# USART.net
KiCad netlist of a schematic drawn in Altium Designer
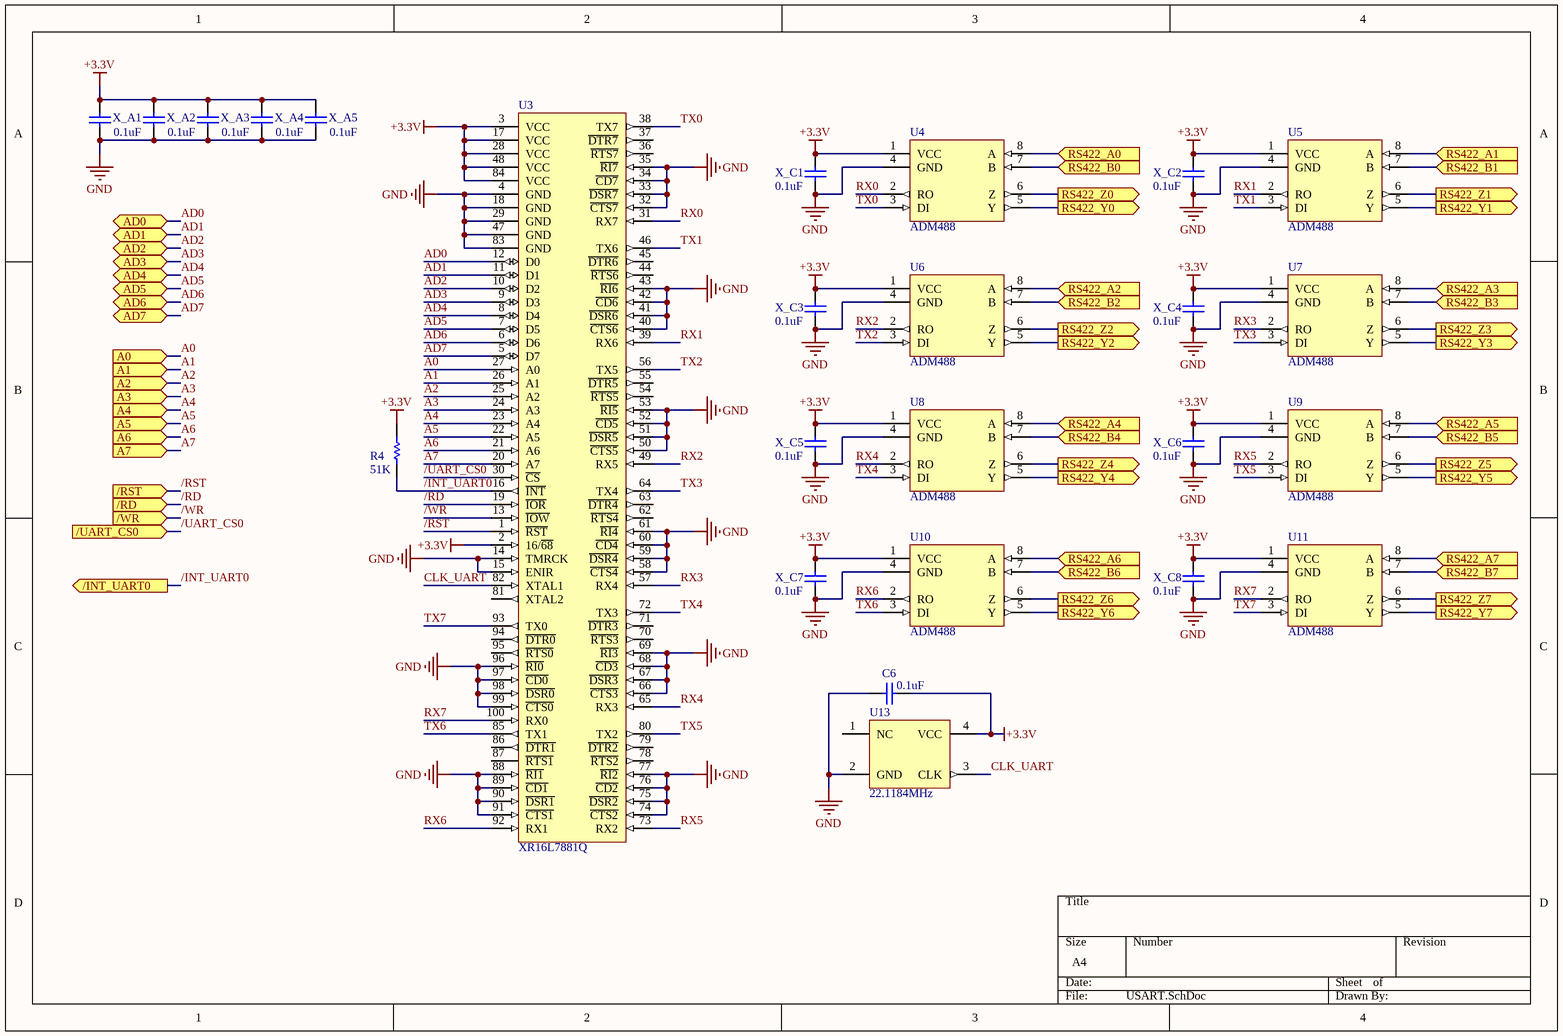
[diagram p0: USART.SchDoc]

(export (version "E")
  (design (tool "Eeschema 10.0.6"))
  (components
    (comp (ref "C6")
      (value "0.1uF")
      (footprint "0805")
      (description "Capacitor")
      (fields (field (name "Comment") "Cap 0.1uf") (field (name "PUBLISHER") "Altium Limited"))
      (libsource (lib "Miscellaneous Devices") (part "Cap"))
    )
    (comp (ref "R4")
      (value "51K")
      (footprint "0805")
      (description "Resistor")
      (fields (field (name "Comment") "51k") (field (name "PUBLISHER") "Altium Limited"))
      (libsource (lib "Miscellaneous Devices") (part "Res1"))
    )
    (comp (ref "U3")
      (value "XR16L7881Q")
      (footprint "QFP65P1800X2400X300-100N_30*20")
      (libsource (lib "cs_Schlib1") (part "my_XR16L7881Q"))
    )
    (comp (ref "U4") (value "ADM488") (footprint "SO-8_L") (libsource (lib "cs_Schlib1") (part "my_ADM488")))
    (comp (ref "U5") (value "ADM488") (footprint "SO-8_L") (libsource (lib "cs_Schlib1") (part "my_ADM488")))
    (comp (ref "U6") (value "ADM488") (footprint "SO-8_L") (libsource (lib "cs_Schlib1") (part "my_ADM488")))
    (comp (ref "U7") (value "ADM488") (footprint "SO-8_L") (libsource (lib "cs_Schlib1") (part "my_ADM488")))
    (comp (ref "U8") (value "ADM488") (footprint "SO-8_L") (libsource (lib "cs_Schlib1") (part "my_ADM488")))
    (comp (ref "U9") (value "ADM488") (footprint "SO-8_L") (libsource (lib "cs_Schlib1") (part "my_ADM488")))
    (comp (ref "U10") (value "ADM488") (footprint "SO-8_L") (libsource (lib "cs_Schlib1") (part "my_ADM488")))
    (comp (ref "U11") (value "ADM488") (footprint "SO-8_L") (libsource (lib "cs_Schlib1") (part "my_ADM488")))
    (comp (ref "U13")
      (value "22.1184MHz")
      (footprint "my_SiT8103")
      (libsource (lib "cs_Schlib1") (part "my_SiT8103"))
    )
    (comp (ref "X_A1")
      (value "0.1uF")
      (footprint "0805")
      (description "Capacitor")
      (fields (field (name "Comment") "Cap 0.1uf") (field (name "PUBLISHER") "Altium Limited"))
      (libsource (lib "Miscellaneous Devices") (part "Cap"))
    )
    (comp (ref "X_A2")
      (value "0.1uF")
      (footprint "0805")
      (description "Capacitor")
      (fields (field (name "Comment") "Cap 0.1uf") (field (name "PUBLISHER") "Altium Limited"))
      (libsource (lib "Miscellaneous Devices") (part "Cap"))
    )
    (comp (ref "X_A3")
      (value "0.1uF")
      (footprint "0805")
      (description "Capacitor")
      (fields (field (name "Comment") "Cap 0.1uf") (field (name "PUBLISHER") "Altium Limited"))
      (libsource (lib "Miscellaneous Devices") (part "Cap"))
    )
    (comp (ref "X_A4")
      (value "0.1uF")
      (footprint "0805")
      (description "Capacitor")
      (fields (field (name "Comment") "Cap 0.1uf") (field (name "PUBLISHER") "Altium Limited"))
      (libsource (lib "Miscellaneous Devices") (part "Cap"))
    )
    (comp (ref "X_A5")
      (value "0.1uF")
      (footprint "0805")
      (description "Capacitor")
      (fields (field (name "Comment") "Cap 0.1uf") (field (name "PUBLISHER") "Altium Limited"))
      (libsource (lib "Miscellaneous Devices") (part "Cap"))
    )
    (comp (ref "X_C1")
      (value "0.1uF")
      (footprint "0805")
      (description "Capacitor")
      (fields (field (name "Comment") "Cap 0.1uf") (field (name "PUBLISHER") "Altium Limited"))
      (libsource (lib "Miscellaneous Devices") (part "Cap"))
    )
    (comp (ref "X_C2")
      (value "0.1uF")
      (footprint "0805")
      (description "Capacitor")
      (fields (field (name "Comment") "Cap 0.1uf") (field (name "PUBLISHER") "Altium Limited"))
      (libsource (lib "Miscellaneous Devices") (part "Cap"))
    )
    (comp (ref "X_C3")
      (value "0.1uF")
      (footprint "0805")
      (description "Capacitor")
      (fields (field (name "Comment") "Cap 0.1uf") (field (name "PUBLISHER") "Altium Limited"))
      (libsource (lib "Miscellaneous Devices") (part "Cap"))
    )
    (comp (ref "X_C4")
      (value "0.1uF")
      (footprint "0805")
      (description "Capacitor")
      (fields (field (name "Comment") "Cap 0.1uf") (field (name "PUBLISHER") "Altium Limited"))
      (libsource (lib "Miscellaneous Devices") (part "Cap"))
    )
    (comp (ref "X_C5")
      (value "0.1uF")
      (footprint "0805")
      (description "Capacitor")
      (fields (field (name "Comment") "Cap 0.1uf") (field (name "PUBLISHER") "Altium Limited"))
      (libsource (lib "Miscellaneous Devices") (part "Cap"))
    )
    (comp (ref "X_C6")
      (value "0.1uF")
      (footprint "0805")
      (description "Capacitor")
      (fields (field (name "Comment") "Cap 0.1uf") (field (name "PUBLISHER") "Altium Limited"))
      (libsource (lib "Miscellaneous Devices") (part "Cap"))
    )
    (comp (ref "X_C7")
      (value "0.1uF")
      (footprint "0805")
      (description "Capacitor")
      (fields (field (name "Comment") "Cap 0.1uf") (field (name "PUBLISHER") "Altium Limited"))
      (libsource (lib "Miscellaneous Devices") (part "Cap"))
    )
    (comp (ref "X_C8")
      (value "0.1uF")
      (footprint "0805")
      (description "Capacitor")
      (fields (field (name "Comment") "Cap 0.1uf") (field (name "PUBLISHER") "Altium Limited"))
      (libsource (lib "Miscellaneous Devices") (part "Cap"))
    )
  )
  (nets
    (net (code "1") (name "+3.3V") (class "Default")
      (node (ref "C6") (pin "1") (pinfunction "1_1") (pintype "passive"))
      (node (ref "R4") (pin "2") (pinfunction "2_2") (pintype "passive"))
      (node (ref "U10") (pin "1") (pinfunction "VCC_1") (pintype "power_in"))
      (node (ref "U11") (pin "1") (pinfunction "VCC_1") (pintype "power_in"))
      (node (ref "U13") (pin "4") (pinfunction "VCC_4") (pintype "power_in"))
      (node (ref "U3") (pin "17") (pinfunction "VCC_17") (pintype "power_in"))
      (node (ref "U3") (pin "2") (pinfunction "16/~{68}_2") (pintype "input"))
      (node (ref "U3") (pin "28") (pinfunction "VCC_28") (pintype "power_in"))
      (node (ref "U3") (pin "3") (pinfunction "VCC_3") (pintype "power_in"))
      (node (ref "U3") (pin "48") (pinfunction "VCC_48") (pintype "power_in"))
      (node (ref "U3") (pin "84") (pinfunction "VCC_84") (pintype "power_in"))
      (node (ref "U4") (pin "1") (pinfunction "VCC_1") (pintype "power_in"))
      (node (ref "U5") (pin "1") (pinfunction "VCC_1") (pintype "power_in"))
      (node (ref "U6") (pin "1") (pinfunction "VCC_1") (pintype "power_in"))
      (node (ref "U7") (pin "1") (pinfunction "VCC_1") (pintype "power_in"))
      (node (ref "U8") (pin "1") (pinfunction "VCC_1") (pintype "power_in"))
      (node (ref "U9") (pin "1") (pinfunction "VCC_1") (pintype "power_in"))
      (node (ref "X_A1") (pin "2") (pinfunction "2_2") (pintype "passive"))
      (node (ref "X_A2") (pin "2") (pinfunction "2_2") (pintype "passive"))
      (node (ref "X_A3") (pin "2") (pinfunction "2_2") (pintype "passive"))
      (node (ref "X_A4") (pin "2") (pinfunction "2_2") (pintype "passive"))
      (node (ref "X_A5") (pin "2") (pinfunction "2_2") (pintype "passive"))
      (node (ref "X_C1") (pin "2") (pinfunction "2_2") (pintype "passive"))
      (node (ref "X_C2") (pin "2") (pinfunction "2_2") (pintype "passive"))
      (node (ref "X_C3") (pin "2") (pinfunction "2_2") (pintype "passive"))
      (node (ref "X_C4") (pin "2") (pinfunction "2_2") (pintype "passive"))
      (node (ref "X_C5") (pin "2") (pinfunction "2_2") (pintype "passive"))
      (node (ref "X_C6") (pin "2") (pinfunction "2_2") (pintype "passive"))
      (node (ref "X_C7") (pin "2") (pinfunction "2_2") (pintype "passive"))
      (node (ref "X_C8") (pin "2") (pinfunction "2_2") (pintype "passive"))
    )
    (net (code "2") (name "/A0") (class "Default")
      (node (ref "U3") (pin "27") (pinfunction "A0_27") (pintype "input"))
    )
    (net (code "3") (name "/A1") (class "Default")
      (node (ref "U3") (pin "26") (pinfunction "A1_26") (pintype "input"))
    )
    (net (code "4") (name "/A2") (class "Default")
      (node (ref "U3") (pin "25") (pinfunction "A2_25") (pintype "input"))
    )
    (net (code "5") (name "/A3") (class "Default")
      (node (ref "U3") (pin "24") (pinfunction "A3_24") (pintype "input"))
    )
    (net (code "6") (name "/A4") (class "Default")
      (node (ref "U3") (pin "23") (pinfunction "A4_23") (pintype "input"))
    )
    (net (code "7") (name "/A5") (class "Default")
      (node (ref "U3") (pin "22") (pinfunction "A5_22") (pintype "input"))
    )
    (net (code "8") (name "/A6") (class "Default")
      (node (ref "U3") (pin "21") (pinfunction "A6_21") (pintype "input"))
    )
    (net (code "9") (name "/A7") (class "Default")
      (node (ref "U3") (pin "20") (pinfunction "A7_20") (pintype "input"))
    )
    (net (code "10") (name "/AD0") (class "Default")
      (node (ref "U3") (pin "12") (pinfunction "D0_12") (pintype "bidirectional"))
    )
    (net (code "11") (name "/AD1") (class "Default")
      (node (ref "U3") (pin "11") (pinfunction "D1_11") (pintype "bidirectional"))
    )
    (net (code "12") (name "/AD2") (class "Default")
      (node (ref "U3") (pin "10") (pinfunction "D2_10") (pintype "bidirectional"))
    )
    (net (code "13") (name "/AD3") (class "Default")
      (node (ref "U3") (pin "9") (pinfunction "D3_9") (pintype "bidirectional"))
    )
    (net (code "14") (name "/AD4") (class "Default")
      (node (ref "U3") (pin "8") (pinfunction "D4_8") (pintype "bidirectional"))
    )
    (net (code "15") (name "/AD5") (class "Default")
      (node (ref "U3") (pin "7") (pinfunction "D5_7") (pintype "bidirectional"))
    )
    (net (code "16") (name "/AD6") (class "Default")
      (node (ref "U3") (pin "6") (pinfunction "D6_6") (pintype "bidirectional"))
    )
    (net (code "17") (name "/AD7") (class "Default")
      (node (ref "U3") (pin "5") (pinfunction "D7_5") (pintype "bidirectional"))
    )
    (net (code "18") (name "/CLK_UART") (class "Default")
      (node (ref "U13") (pin "3") (pinfunction "CLK_3") (pintype "output"))
      (node (ref "U3") (pin "82") (pinfunction "XTAL1_82") (pintype "input"))
    )
    (net (code "19") (name "/RS422_A0") (class "Default")
      (node (ref "U4") (pin "8") (pinfunction "A_8") (pintype "input"))
    )
    (net (code "20") (name "/RS422_A1") (class "Default")
      (node (ref "U5") (pin "8") (pinfunction "A_8") (pintype "input"))
    )
    (net (code "21") (name "/RS422_A2") (class "Default")
      (node (ref "U6") (pin "8") (pinfunction "A_8") (pintype "input"))
    )
    (net (code "22") (name "/RS422_A3") (class "Default")
      (node (ref "U7") (pin "8") (pinfunction "A_8") (pintype "input"))
    )
    (net (code "23") (name "/RS422_A4") (class "Default")
      (node (ref "U8") (pin "8") (pinfunction "A_8") (pintype "input"))
    )
    (net (code "24") (name "/RS422_A5") (class "Default")
      (node (ref "U9") (pin "8") (pinfunction "A_8") (pintype "input"))
    )
    (net (code "25") (name "/RS422_A6") (class "Default")
      (node (ref "U10") (pin "8") (pinfunction "A_8") (pintype "input"))
    )
    (net (code "26") (name "/RS422_A7") (class "Default")
      (node (ref "U11") (pin "8") (pinfunction "A_8") (pintype "input"))
    )
    (net (code "27") (name "/RS422_B0") (class "Default")
      (node (ref "U4") (pin "7") (pinfunction "B_7") (pintype "input"))
    )
    (net (code "28") (name "/RS422_B1") (class "Default")
      (node (ref "U5") (pin "7") (pinfunction "B_7") (pintype "input"))
    )
    (net (code "29") (name "/RS422_B2") (class "Default")
      (node (ref "U6") (pin "7") (pinfunction "B_7") (pintype "input"))
    )
    (net (code "30") (name "/RS422_B3") (class "Default")
      (node (ref "U7") (pin "7") (pinfunction "B_7") (pintype "input"))
    )
    (net (code "31") (name "/RS422_B4") (class "Default")
      (node (ref "U8") (pin "7") (pinfunction "B_7") (pintype "input"))
    )
    (net (code "32") (name "/RS422_B5") (class "Default")
      (node (ref "U9") (pin "7") (pinfunction "B_7") (pintype "input"))
    )
    (net (code "33") (name "/RS422_B6") (class "Default")
      (node (ref "U10") (pin "7") (pinfunction "B_7") (pintype "input"))
    )
    (net (code "34") (name "/RS422_B7") (class "Default")
      (node (ref "U11") (pin "7") (pinfunction "B_7") (pintype "input"))
    )
    (net (code "35") (name "/RS422_Y0") (class "Default")
      (node (ref "U4") (pin "5") (pinfunction "Y_5") (pintype "output"))
    )
    (net (code "36") (name "/RS422_Y1") (class "Default")
      (node (ref "U5") (pin "5") (pinfunction "Y_5") (pintype "output"))
    )
    (net (code "37") (name "/RS422_Y2") (class "Default")
      (node (ref "U6") (pin "5") (pinfunction "Y_5") (pintype "output"))
    )
    (net (code "38") (name "/RS422_Y3") (class "Default")
      (node (ref "U7") (pin "5") (pinfunction "Y_5") (pintype "output"))
    )
    (net (code "39") (name "/RS422_Y4") (class "Default")
      (node (ref "U8") (pin "5") (pinfunction "Y_5") (pintype "output"))
    )
    (net (code "40") (name "/RS422_Y5") (class "Default")
      (node (ref "U9") (pin "5") (pinfunction "Y_5") (pintype "output"))
    )
    (net (code "41") (name "/RS422_Y6") (class "Default")
      (node (ref "U10") (pin "5") (pinfunction "Y_5") (pintype "output"))
    )
    (net (code "42") (name "/RS422_Y7") (class "Default")
      (node (ref "U11") (pin "5") (pinfunction "Y_5") (pintype "output"))
    )
    (net (code "43") (name "/RS422_Z0") (class "Default")
      (node (ref "U4") (pin "6") (pinfunction "Z_6") (pintype "output"))
    )
    (net (code "44") (name "/RS422_Z1") (class "Default")
      (node (ref "U5") (pin "6") (pinfunction "Z_6") (pintype "output"))
    )
    (net (code "45") (name "/RS422_Z2") (class "Default")
      (node (ref "U6") (pin "6") (pinfunction "Z_6") (pintype "output"))
    )
    (net (code "46") (name "/RS422_Z3") (class "Default")
      (node (ref "U7") (pin "6") (pinfunction "Z_6") (pintype "output"))
    )
    (net (code "47") (name "/RS422_Z4") (class "Default")
      (node (ref "U8") (pin "6") (pinfunction "Z_6") (pintype "output"))
    )
    (net (code "48") (name "/RS422_Z5") (class "Default")
      (node (ref "U9") (pin "6") (pinfunction "Z_6") (pintype "output"))
    )
    (net (code "49") (name "/RS422_Z6") (class "Default")
      (node (ref "U10") (pin "6") (pinfunction "Z_6") (pintype "output"))
    )
    (net (code "50") (name "/RS422_Z7") (class "Default")
      (node (ref "U11") (pin "6") (pinfunction "Z_6") (pintype "output"))
    )
    (net (code "51") (name "/RX0") (class "Default")
      (node (ref "U3") (pin "31") (pinfunction "RX7_31") (pintype "input"))
      (node (ref "U4") (pin "2") (pinfunction "RO_2") (pintype "output"))
    )
    (net (code "52") (name "/RX1") (class "Default")
      (node (ref "U3") (pin "39") (pinfunction "RX6_39") (pintype "input"))
      (node (ref "U5") (pin "2") (pinfunction "RO_2") (pintype "output"))
    )
    (net (code "53") (name "/RX2") (class "Default")
      (node (ref "U3") (pin "49") (pinfunction "RX5_49") (pintype "input"))
      (node (ref "U6") (pin "2") (pinfunction "RO_2") (pintype "output"))
    )
    (net (code "54") (name "/RX3") (class "Default")
      (node (ref "U3") (pin "57") (pinfunction "RX4_57") (pintype "input"))
      (node (ref "U7") (pin "2") (pinfunction "RO_2") (pintype "output"))
    )
    (net (code "55") (name "/RX4") (class "Default")
      (node (ref "U3") (pin "65") (pinfunction "RX3_65") (pintype "input"))
      (node (ref "U8") (pin "2") (pinfunction "RO_2") (pintype "output"))
    )
    (net (code "56") (name "/RX5") (class "Default")
      (node (ref "U3") (pin "73") (pinfunction "RX2_73") (pintype "input"))
      (node (ref "U9") (pin "2") (pinfunction "RO_2") (pintype "output"))
    )
    (net (code "57") (name "/RX6") (class "Default")
      (node (ref "U10") (pin "2") (pinfunction "RO_2") (pintype "output"))
      (node (ref "U3") (pin "92") (pinfunction "RX1_92") (pintype "input"))
    )
    (net (code "58") (name "/RX7") (class "Default")
      (node (ref "U11") (pin "2") (pinfunction "RO_2") (pintype "output"))
      (node (ref "U3") (pin "100") (pinfunction "RX0_100") (pintype "input"))
    )
    (net (code "59") (name "/TX0") (class "Default")
      (node (ref "U3") (pin "38") (pinfunction "TX7_38") (pintype "output"))
      (node (ref "U4") (pin "3") (pinfunction "DI_3") (pintype "input"))
    )
    (net (code "60") (name "/TX1") (class "Default")
      (node (ref "U3") (pin "46") (pinfunction "TX6_46") (pintype "output"))
      (node (ref "U5") (pin "3") (pinfunction "DI_3") (pintype "input"))
    )
    (net (code "61") (name "/TX2") (class "Default")
      (node (ref "U3") (pin "56") (pinfunction "TX5_56") (pintype "output"))
      (node (ref "U6") (pin "3") (pinfunction "DI_3") (pintype "input"))
    )
    (net (code "62") (name "/TX3") (class "Default")
      (node (ref "U3") (pin "64") (pinfunction "TX4_64") (pintype "output"))
      (node (ref "U7") (pin "3") (pinfunction "DI_3") (pintype "input"))
    )
    (net (code "63") (name "/TX4") (class "Default")
      (node (ref "U3") (pin "72") (pinfunction "TX3_72") (pintype "output"))
      (node (ref "U8") (pin "3") (pinfunction "DI_3") (pintype "input"))
    )
    (net (code "64") (name "/TX5") (class "Default")
      (node (ref "U3") (pin "80") (pinfunction "TX2_80") (pintype "output"))
      (node (ref "U9") (pin "3") (pinfunction "DI_3") (pintype "input"))
    )
    (net (code "65") (name "/TX6") (class "Default")
      (node (ref "U10") (pin "3") (pinfunction "DI_3") (pintype "input"))
      (node (ref "U3") (pin "85") (pinfunction "TX1_85") (pintype "output"))
    )
    (net (code "66") (name "/TX7") (class "Default")
      (node (ref "U11") (pin "3") (pinfunction "DI_3") (pintype "input"))
      (node (ref "U3") (pin "93") (pinfunction "TX0_93") (pintype "output"))
    )
    (net (code "67") (name "/{slash}INT_UART0") (class "Default")
      (node (ref "R4") (pin "1") (pinfunction "1_1") (pintype "passive"))
      (node (ref "U3") (pin "16") (pinfunction "~{INT}_16") (pintype "output"))
    )
    (net (code "68") (name "/{slash}RD") (class "Default")
      (node (ref "U3") (pin "19") (pinfunction "~{IOR}_19") (pintype "input"))
    )
    (net (code "69") (name "/{slash}RST") (class "Default")
      (node (ref "U3") (pin "1") (pinfunction "~{RST}_1") (pintype "input"))
    )
    (net (code "70") (name "/{slash}UART_CS0") (class "Default")
      (node (ref "U3") (pin "30") (pinfunction "~{CS}_30") (pintype "input"))
    )
    (net (code "71") (name "/{slash}WR") (class "Default")
      (node (ref "U3") (pin "13") (pinfunction "~{IOW}_13") (pintype "input"))
    )
    (net (code "72") (name "GND") (class "Default")
      (node (ref "C6") (pin "2") (pinfunction "2_2") (pintype "passive"))
      (node (ref "U10") (pin "4") (pinfunction "GND_4") (pintype "power_in"))
      (node (ref "U11") (pin "4") (pinfunction "GND_4") (pintype "power_in"))
      (node (ref "U13") (pin "2") (pinfunction "GND_2") (pintype "power_in"))
      (node (ref "U3") (pin "14") (pinfunction "TMRCK_14") (pintype "input"))
      (node (ref "U3") (pin "15") (pinfunction "ENIR_15") (pintype "input"))
      (node (ref "U3") (pin "18") (pinfunction "GND_18") (pintype "power_in"))
      (node (ref "U3") (pin "29") (pinfunction "GND_29") (pintype "power_in"))
      (node (ref "U3") (pin "32") (pinfunction "~{CTS7}_32") (pintype "input"))
      (node (ref "U3") (pin "33") (pinfunction "~{DSR7}_33") (pintype "input"))
      (node (ref "U3") (pin "34") (pinfunction "~{CD7}_34") (pintype "input"))
      (node (ref "U3") (pin "35") (pinfunction "~{RI7}_35") (pintype "input"))
      (node (ref "U3") (pin "4") (pinfunction "GND_4") (pintype "power_in"))
      (node (ref "U3") (pin "40") (pinfunction "~{CTS6}_40") (pintype "input"))
      (node (ref "U3") (pin "41") (pinfunction "~{DSR6}_41") (pintype "input"))
      (node (ref "U3") (pin "42") (pinfunction "~{CD6}_42") (pintype "input"))
      (node (ref "U3") (pin "43") (pinfunction "~{RI6}_43") (pintype "input"))
      (node (ref "U3") (pin "47") (pinfunction "GND_47") (pintype "passive"))
      (node (ref "U3") (pin "50") (pinfunction "~{CTS5}_50") (pintype "input"))
      (node (ref "U3") (pin "51") (pinfunction "~{DSR5}_51") (pintype "input"))
      (node (ref "U3") (pin "52") (pinfunction "~{CD5}_52") (pintype "input"))
      (node (ref "U3") (pin "53") (pinfunction "~{RI5}_53") (pintype "input"))
      (node (ref "U3") (pin "58") (pinfunction "~{CTS4}_58") (pintype "input"))
      (node (ref "U3") (pin "59") (pinfunction "~{DSR4}_59") (pintype "input"))
      (node (ref "U3") (pin "60") (pinfunction "~{CD4}_60") (pintype "input"))
      (node (ref "U3") (pin "61") (pinfunction "~{RI4}_61") (pintype "input"))
      (node (ref "U3") (pin "66") (pinfunction "~{CTS3}_66") (pintype "input"))
      (node (ref "U3") (pin "67") (pinfunction "~{DSR3}_67") (pintype "input"))
      (node (ref "U3") (pin "68") (pinfunction "~{CD3}_68") (pintype "input"))
      (node (ref "U3") (pin "69") (pinfunction "~{RI3}_69") (pintype "input"))
      (node (ref "U3") (pin "74") (pinfunction "~{CTS2}_74") (pintype "input"))
      (node (ref "U3") (pin "75") (pinfunction "~{DSR2}_75") (pintype "input"))
      (node (ref "U3") (pin "76") (pinfunction "~{CD2}_76") (pintype "input"))
      (node (ref "U3") (pin "77") (pinfunction "~{RI2}_77") (pintype "input"))
      (node (ref "U3") (pin "83") (pinfunction "GND_83") (pintype "passive"))
      (node (ref "U3") (pin "88") (pinfunction "~{RI1}_88") (pintype "input"))
      (node (ref "U3") (pin "89") (pinfunction "~{CD1}_89") (pintype "input"))
      (node (ref "U3") (pin "90") (pinfunction "~{DSR1}_90") (pintype "input"))
      (node (ref "U3") (pin "91") (pinfunction "~{CTS1}_91") (pintype "input"))
      (node (ref "U3") (pin "96") (pinfunction "~{RI0}_96") (pintype "input"))
      (node (ref "U3") (pin "97") (pinfunction "~{CD0}_97") (pintype "input"))
      (node (ref "U3") (pin "98") (pinfunction "~{DSR0}_98") (pintype "input"))
      (node (ref "U3") (pin "99") (pinfunction "~{CTS0}_99") (pintype "input"))
      (node (ref "U4") (pin "4") (pinfunction "GND_4") (pintype "power_in"))
      (node (ref "U5") (pin "4") (pinfunction "GND_4") (pintype "power_in"))
      (node (ref "U6") (pin "4") (pinfunction "GND_4") (pintype "power_in"))
      (node (ref "U7") (pin "4") (pinfunction "GND_4") (pintype "power_in"))
      (node (ref "U8") (pin "4") (pinfunction "GND_4") (pintype "power_in"))
      (node (ref "U9") (pin "4") (pinfunction "GND_4") (pintype "power_in"))
      (node (ref "X_A1") (pin "1") (pinfunction "1_1") (pintype "passive"))
      (node (ref "X_A2") (pin "1") (pinfunction "1_1") (pintype "passive"))
      (node (ref "X_A3") (pin "1") (pinfunction "1_1") (pintype "passive"))
      (node (ref "X_A4") (pin "1") (pinfunction "1_1") (pintype "passive"))
      (node (ref "X_A5") (pin "1") (pinfunction "1_1") (pintype "passive"))
      (node (ref "X_C1") (pin "1") (pinfunction "1_1") (pintype "passive"))
      (node (ref "X_C2") (pin "1") (pinfunction "1_1") (pintype "passive"))
      (node (ref "X_C3") (pin "1") (pinfunction "1_1") (pintype "passive"))
      (node (ref "X_C4") (pin "1") (pinfunction "1_1") (pintype "passive"))
      (node (ref "X_C5") (pin "1") (pinfunction "1_1") (pintype "passive"))
      (node (ref "X_C6") (pin "1") (pinfunction "1_1") (pintype "passive"))
      (node (ref "X_C7") (pin "1") (pinfunction "1_1") (pintype "passive"))
      (node (ref "X_C8") (pin "1") (pinfunction "1_1") (pintype "passive"))
    )
    (net (code "73") (name "unconnected-(U3-XTAL2-Pad81)") (class "Default")
      (node (ref "U3") (pin "81") (pinfunction "XTAL2_81") (pintype "output"))
    )
    (net (code "74") (name "unconnected-(U3-~{DTR0}-Pad94)") (class "Default")
      (node (ref "U3") (pin "94") (pinfunction "~{DTR0}_94") (pintype "output"))
    )
    (net (code "75") (name "unconnected-(U3-~{DTR1}-Pad86)") (class "Default")
      (node (ref "U3") (pin "86") (pinfunction "~{DTR1}_86") (pintype "output"))
    )
    (net (code "76") (name "unconnected-(U3-~{DTR2}-Pad79)") (class "Default")
      (node (ref "U3") (pin "79") (pinfunction "~{DTR2}_79") (pintype "output"))
    )
    (net (code "77") (name "unconnected-(U3-~{DTR3}-Pad71)") (class "Default")
      (node (ref "U3") (pin "71") (pinfunction "~{DTR3}_71") (pintype "output"))
    )
    (net (code "78") (name "unconnected-(U3-~{DTR4}-Pad63)") (class "Default")
      (node (ref "U3") (pin "63") (pinfunction "~{DTR4}_63") (pintype "output"))
    )
    (net (code "79") (name "unconnected-(U3-~{DTR5}-Pad55)") (class "Default")
      (node (ref "U3") (pin "55") (pinfunction "~{DTR5}_55") (pintype "output"))
    )
    (net (code "80") (name "unconnected-(U3-~{DTR6}-Pad45)") (class "Default")
      (node (ref "U3") (pin "45") (pinfunction "~{DTR6}_45") (pintype "output"))
    )
    (net (code "81") (name "unconnected-(U3-~{DTR7}-Pad37)") (class "Default")
      (node (ref "U3") (pin "37") (pinfunction "~{DTR7}_37") (pintype "output"))
    )
    (net (code "82") (name "unconnected-(U3-~{RTS0}-Pad95)") (class "Default")
      (node (ref "U3") (pin "95") (pinfunction "~{RTS0}_95") (pintype "output"))
    )
    (net (code "83") (name "unconnected-(U3-~{RTS1}-Pad87)") (class "Default")
      (node (ref "U3") (pin "87") (pinfunction "~{RTS1}_87") (pintype "passive"))
    )
    (net (code "84") (name "unconnected-(U3-~{RTS2}-Pad78)") (class "Default")
      (node (ref "U3") (pin "78") (pinfunction "~{RTS2}_78") (pintype "output"))
    )
    (net (code "85") (name "unconnected-(U3-~{RTS3}-Pad70)") (class "Default")
      (node (ref "U3") (pin "70") (pinfunction "~{RTS3}_70") (pintype "output"))
    )
    (net (code "86") (name "unconnected-(U3-~{RTS4}-Pad62)") (class "Default")
      (node (ref "U3") (pin "62") (pinfunction "~{RTS4}_62") (pintype "output"))
    )
    (net (code "87") (name "unconnected-(U3-~{RTS5}-Pad54)") (class "Default")
      (node (ref "U3") (pin "54") (pinfunction "~{RTS5}_54") (pintype "output"))
    )
    (net (code "88") (name "unconnected-(U3-~{RTS6}-Pad44)") (class "Default")
      (node (ref "U3") (pin "44") (pinfunction "~{RTS6}_44") (pintype "output"))
    )
    (net (code "89") (name "unconnected-(U3-~{RTS7}-Pad36)") (class "Default")
      (node (ref "U3") (pin "36") (pinfunction "~{RTS7}_36") (pintype "output"))
    )
    (net (code "90") (name "unconnected-(U13-NC-Pad1)") (class "Default")
      (node (ref "U13") (pin "1") (pinfunction "NC_1") (pintype "passive"))
    )
  )
)
